# shield.net
KiCad netlist of a schematic drawn in EAGLE
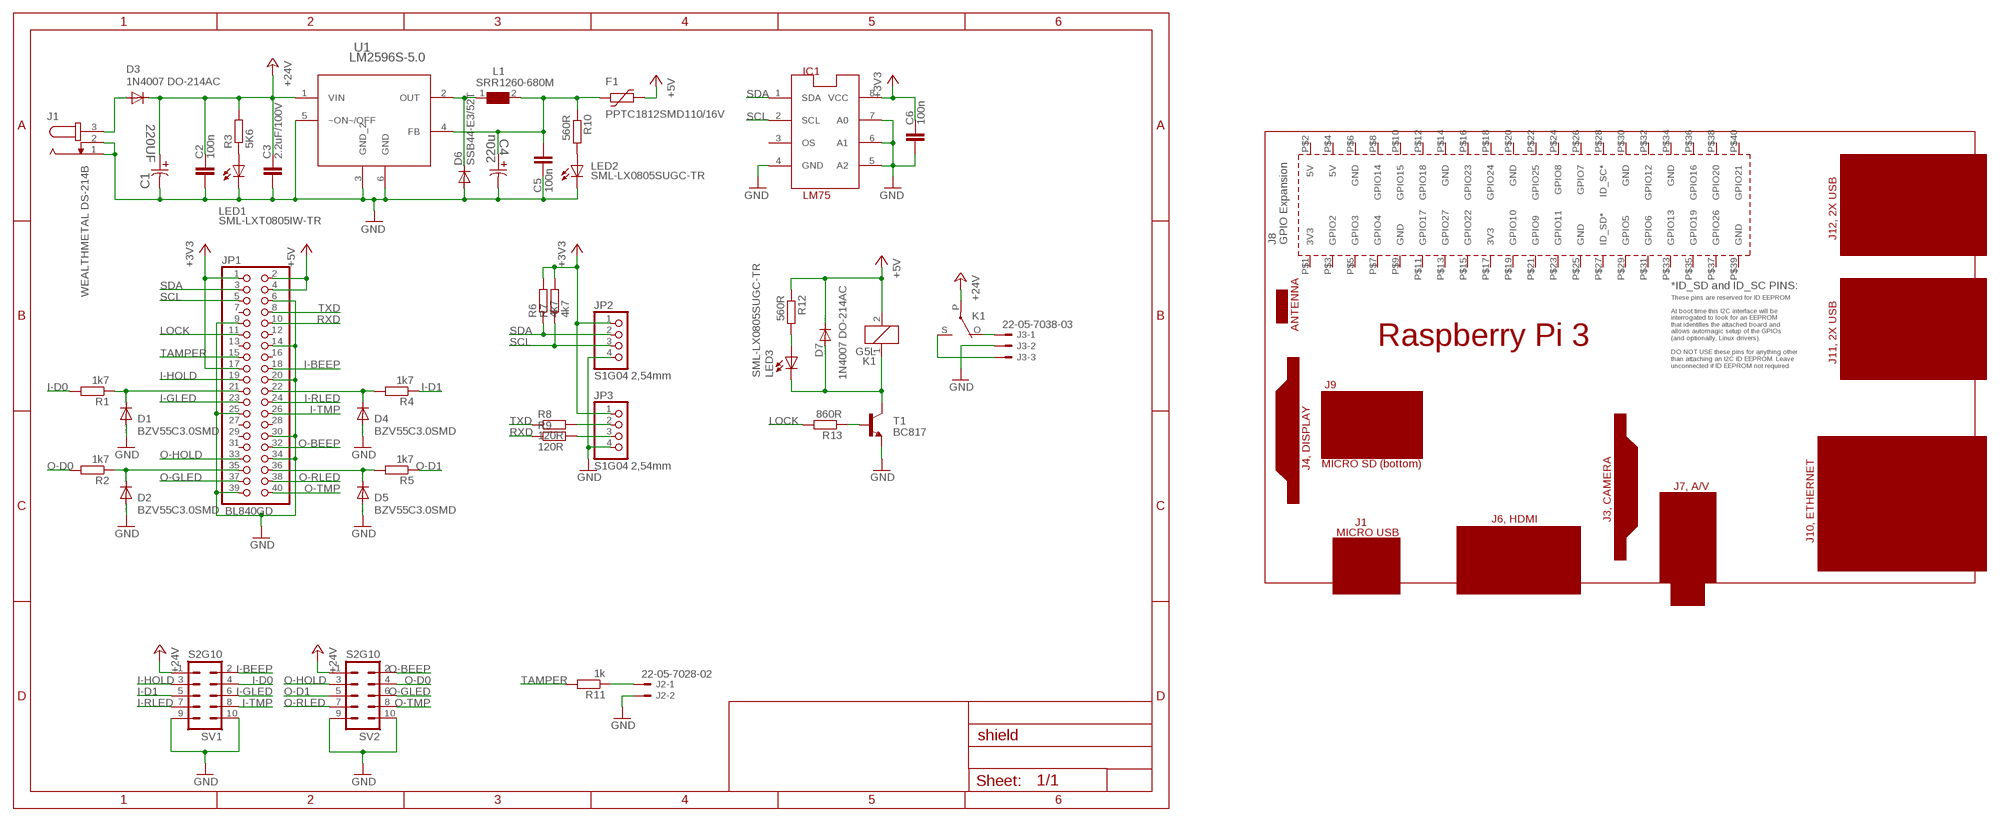
[diagram p0: schematic, sheet 1]

(export (version "E")
  (design (tool "Eeschema 10.0.6"))
  (components
    (comp (ref "C1")
      (value "220UF")
      (footprint "eagle-import:CAPAE830X1050N")
      (fields (field (name "MPN") "EEE-FP1V221AP") (field (name "TOLERANCE") "±20 %"))
      (libsource (lib "eagle-import") (part "EEE--CASE-FFP1V221AP"))
    )
    (comp (ref "C2")
      (value "100n")
      (footprint "eagle-import:C0805")
      (libsource (lib "eagle-import") (part "C-EUC0805"))
    )
    (comp (ref "C3")
      (value "2.2uF/100V")
      (footprint "eagle-import:C1206")
      (libsource (lib "eagle-import") (part "C-EUC1206"))
    )
    (comp (ref "C4")
      (value "220u")
      (footprint "eagle-import:CAPAE830X1050N")
      (fields (field (name "MPN") "EEE-FP1V221AP") (field (name "TOLERANCE") "±20 %"))
      (libsource (lib "eagle-import") (part "EEE--CASE-FFP1V221AP"))
    )
    (comp (ref "C5")
      (value "100n")
      (footprint "eagle-import:C0805")
      (libsource (lib "eagle-import") (part "C-EUC0805"))
    )
    (comp (ref "C6")
      (value "100n")
      (footprint "eagle-import:C0805")
      (libsource (lib "eagle-import") (part "C-EUC0805"))
    )
    (comp (ref "D1")
      (value "BZV55C3.0SMD")
      (footprint "eagle-import:MINIMELF")
      (libsource (lib "eagle-import") (part "DIODE-MINIMELF"))
    )
    (comp (ref "D2")
      (value "BZV55C3.0SMD")
      (footprint "eagle-import:MINIMELF")
      (libsource (lib "eagle-import") (part "DIODE-MINIMELF"))
    )
    (comp (ref "D3")
      (value "1N4007 DO-214AC")
      (footprint "eagle-import:DO-214AC")
      (libsource (lib "eagle-import") (part "DIODE-DO-214AC"))
    )
    (comp (ref "D4")
      (value "BZV55C3.0SMD")
      (footprint "eagle-import:MINIMELF")
      (libsource (lib "eagle-import") (part "DIODE-MINIMELF"))
    )
    (comp (ref "D5")
      (value "BZV55C3.0SMD")
      (footprint "eagle-import:MINIMELF")
      (libsource (lib "eagle-import") (part "DIODE-MINIMELF"))
    )
    (comp (ref "D6")
      (value "SSB44-E3/52T")
      (footprint "eagle-import:DO214AA")
      (libsource (lib "eagle-import") (part "DIODE-DO214AA"))
    )
    (comp (ref "D7")
      (value "1N4007 DO-214AC")
      (footprint "eagle-import:DO-214AC")
      (libsource (lib "eagle-import") (part "DIODE-DO-214AC"))
    )
    (comp (ref "F1")
      (value "PPTC1812SMD110/16V")
      (footprint "eagle-import:1812L")
      (libsource (lib "eagle-import") (part "1812L"))
    )
    (comp (ref "IC1")
      (value "LM75")
      (footprint "eagle-import:SO8_LM75")
      (libsource (lib "eagle-import") (part "LM75_ICN"))
    )
    (comp (ref "J1")
      (value "WEALTHMETAL DS-214B")
      (footprint "eagle-import:SPC4077")
      (libsource (lib "eagle-import") (part "JACK-PLUG0"))
    )
    (comp (ref "J2")
      (value "22-05-7028-02")
      (footprint "eagle-import:7395-02")
      (libsource (lib "eagle-import") (part "22-?-0205-7028"))
    )
    (comp (ref "J3")
      (value "22-05-7038-03")
      (footprint "eagle-import:7395-03")
      (libsource (lib "eagle-import") (part "22-?-0305-7038"))
    )
    (comp (ref "JP1")
      (value "BL840GD")
      (footprint "eagle-import:2X20")
      (libsource (lib "eagle-import") (part "PINHD-2X20"))
    )
    (comp (ref "JP2")
      (value "S1G04 2,54mm")
      (footprint "eagle-import:1X04")
      (libsource (lib "eagle-import") (part "PINHD-1X4"))
    )
    (comp (ref "JP3")
      (value "S1G04 2,54mm")
      (footprint "eagle-import:1X04")
      (libsource (lib "eagle-import") (part "PINHD-1X4"))
    )
    (comp (ref "K1")
      (value "G5L")
      (footprint "eagle-import:G5LE")
      (libsource (lib "eagle-import") (part "G5L"))
    )
    (comp (ref "L1")
      (value "SRR1260-680M")
      (footprint "eagle-import:WE-PD_1260_1245_1280_1210")
      (fields (field (name "MPN") "7447709680"))
      (libsource (lib "eagle-import") (part "WE-PD_1260/1245/1280/1210-7447709680"))
    )
    (comp (ref "LED1")
      (value "SML-LXT0805IW-TR")
      (footprint "eagle-import:CHIPLED_0805")
      (libsource (lib "eagle-import") (part "LEDCHIPLED_0805"))
    )
    (comp (ref "LED2")
      (value "SML-LX0805SUGC-TR")
      (footprint "eagle-import:CHIPLED_0805")
      (libsource (lib "eagle-import") (part "LEDCHIPLED_0805"))
    )
    (comp (ref "LED3")
      (value "SML-LX0805SUGC-TR")
      (footprint "eagle-import:CHIPLED_0805")
      (libsource (lib "eagle-import") (part "LEDCHIPLED_0805"))
    )
    (comp (ref "PCB1")
      (value "RPI3")
      (footprint "eagle-import:RPI3")
      (libsource (lib "eagle-import") (part "RPI3"))
    )
    (comp (ref "R1")
      (value "1k7")
      (footprint "eagle-import:R0805")
      (libsource (lib "eagle-import") (part "R-EU_R0805"))
    )
    (comp (ref "R2")
      (value "1k7")
      (footprint "eagle-import:R0805")
      (libsource (lib "eagle-import") (part "R-EU_R0805"))
    )
    (comp (ref "R3")
      (value "5K6")
      (footprint "eagle-import:R0805")
      (libsource (lib "eagle-import") (part "R-EU_R0805"))
    )
    (comp (ref "R4")
      (value "1k7")
      (footprint "eagle-import:R0805")
      (libsource (lib "eagle-import") (part "R-EU_R0805"))
    )
    (comp (ref "R5")
      (value "1k7")
      (footprint "eagle-import:R0805")
      (libsource (lib "eagle-import") (part "R-EU_R0805"))
    )
    (comp (ref "R6")
      (value "4k7")
      (footprint "eagle-import:R0805")
      (libsource (lib "eagle-import") (part "R-EU_R0805"))
    )
    (comp (ref "R7")
      (value "4k7")
      (footprint "eagle-import:R0805")
      (libsource (lib "eagle-import") (part "R-EU_R0805"))
    )
    (comp (ref "R8")
      (value "120R")
      (footprint "eagle-import:R0805")
      (libsource (lib "eagle-import") (part "R-EU_R0805"))
    )
    (comp (ref "R9")
      (value "120R")
      (footprint "eagle-import:R0805")
      (libsource (lib "eagle-import") (part "R-EU_R0805"))
    )
    (comp (ref "R10")
      (value "560R")
      (footprint "eagle-import:R0805")
      (libsource (lib "eagle-import") (part "R-EU_R0805"))
    )
    (comp (ref "R11")
      (value "1k")
      (footprint "eagle-import:R0805")
      (libsource (lib "eagle-import") (part "R-EU_R0805"))
    )
    (comp (ref "R12")
      (value "560R")
      (footprint "eagle-import:R0805")
      (libsource (lib "eagle-import") (part "R-EU_R0805"))
    )
    (comp (ref "R13")
      (value "860R")
      (footprint "eagle-import:R0805")
      (libsource (lib "eagle-import") (part "R-EU_R0805"))
    )
    (comp (ref "SV1")
      (value "S2G10")
      (footprint "eagle-import:MA05-2")
      (libsource (lib "eagle-import") (part "MA05-2"))
    )
    (comp (ref "SV2")
      (value "S2G10")
      (footprint "eagle-import:MA05-2")
      (libsource (lib "eagle-import") (part "MA05-2"))
    )
    (comp (ref "T1")
      (value "BC817")
      (footprint "eagle-import:SOT23-BEC")
      (libsource (lib "eagle-import") (part "-NPN-SOT23-BECBC817-16"))
    )
    (comp (ref "U1")
      (value "LM2596S-5.0")
      (footprint "eagle-import:TO170P1435X465-6N")
      (fields (field (name "MPN") "LM2596S-50"))
      (libsource (lib "eagle-import") (part "LM2596S-5.0"))
    )
  )
  (nets
    (net (code "1") (name "+3V3") (class "Default")
      (node (ref "C6") (pin "2") (pinfunction "2_2") (pintype "passive"))
      (node (ref "IC1") (pin "8") (pinfunction "VCC_8") (pintype "power_in"))
      (node (ref "JP1") (pin "1") (pinfunction "1_1") (pintype "passive"))
      (node (ref "JP1") (pin "17") (pinfunction "17_17") (pintype "passive"))
      (node (ref "JP2") (pin "1") (pinfunction "1_1") (pintype "passive"))
      (node (ref "JP3") (pin "1") (pinfunction "1_1") (pintype "passive"))
      (node (ref "R6") (pin "2") (pinfunction "2_2") (pintype "passive"))
      (node (ref "R7") (pin "2") (pinfunction "2_2") (pintype "passive"))
    )
    (net (code "2") (name "+5V") (class "Default")
      (node (ref "D7") (pin "C") (pinfunction "C_C") (pintype "passive"))
      (node (ref "F1") (pin "P$2") (pinfunction "2_P$2") (pintype "passive"))
      (node (ref "JP1") (pin "2") (pinfunction "2_2") (pintype "passive"))
      (node (ref "JP1") (pin "4") (pinfunction "4_4") (pintype "passive"))
      (node (ref "K1") (pin "2") (pinfunction "2_2") (pintype "passive"))
      (node (ref "R12") (pin "1") (pinfunction "1_1") (pintype "passive"))
    )
    (net (code "3") (name "+24V") (class "Default")
      (node (ref "C1") (pin "1") (pinfunction "1_1") (pintype "passive"))
      (node (ref "C2") (pin "2") (pinfunction "2_2") (pintype "passive"))
      (node (ref "C3") (pin "1") (pinfunction "1_1") (pintype "passive"))
      (node (ref "D3") (pin "C") (pinfunction "C_C") (pintype "passive"))
      (node (ref "K1") (pin "P") (pinfunction "P_P") (pintype "passive"))
      (node (ref "R3") (pin "2") (pinfunction "2_2") (pintype "passive"))
      (node (ref "SV1") (pin "1") (pinfunction "1_1") (pintype "passive"))
      (node (ref "SV2") (pin "1") (pinfunction "1_1") (pintype "passive"))
      (node (ref "U1") (pin "1") (pinfunction "VIN_1") (pintype "power_in"))
    )
    (net (code "4") (name "/I-BEEP") (class "Default")
      (node (ref "JP1") (pin "18") (pinfunction "18_18") (pintype "passive"))
      (node (ref "SV1") (pin "2") (pinfunction "2_2") (pintype "passive"))
    )
    (net (code "5") (name "/I-D0") (class "Default")
      (node (ref "R1") (pin "2") (pinfunction "2_2") (pintype "passive"))
      (node (ref "SV1") (pin "4") (pinfunction "4_4") (pintype "passive"))
    )
    (net (code "6") (name "/I-D1") (class "Default")
      (node (ref "R4") (pin "1") (pinfunction "1_1") (pintype "passive"))
      (node (ref "SV1") (pin "5") (pinfunction "5_5") (pintype "passive"))
    )
    (net (code "7") (name "/I-GLED") (class "Default")
      (node (ref "JP1") (pin "23") (pinfunction "23_23") (pintype "passive"))
      (node (ref "SV1") (pin "6") (pinfunction "6_6") (pintype "passive"))
    )
    (net (code "8") (name "/I-HOLD") (class "Default")
      (node (ref "JP1") (pin "19") (pinfunction "19_19") (pintype "passive"))
      (node (ref "SV1") (pin "3") (pinfunction "3_3") (pintype "passive"))
    )
    (net (code "9") (name "/I-RLED") (class "Default")
      (node (ref "JP1") (pin "24") (pinfunction "24_24") (pintype "passive"))
      (node (ref "SV1") (pin "7") (pinfunction "7_7") (pintype "passive"))
    )
    (net (code "10") (name "/I-TMP") (class "Default")
      (node (ref "JP1") (pin "26") (pinfunction "26_26") (pintype "passive"))
      (node (ref "SV1") (pin "8") (pinfunction "8_8") (pintype "passive"))
    )
    (net (code "11") (name "/LOCK") (class "Default")
      (node (ref "JP1") (pin "11") (pinfunction "11_11") (pintype "passive"))
      (node (ref "R13") (pin "2") (pinfunction "2_2") (pintype "passive"))
    )
    (net (code "12") (name "/O-BEEP") (class "Default")
      (node (ref "JP1") (pin "32") (pinfunction "32_32") (pintype "passive"))
      (node (ref "SV2") (pin "2") (pinfunction "2_2") (pintype "passive"))
    )
    (net (code "13") (name "/O-D0") (class "Default")
      (node (ref "R2") (pin "2") (pinfunction "2_2") (pintype "passive"))
      (node (ref "SV2") (pin "4") (pinfunction "4_4") (pintype "passive"))
    )
    (net (code "14") (name "/O-D1") (class "Default")
      (node (ref "R5") (pin "1") (pinfunction "1_1") (pintype "passive"))
      (node (ref "SV2") (pin "5") (pinfunction "5_5") (pintype "passive"))
    )
    (net (code "15") (name "/O-GLED") (class "Default")
      (node (ref "JP1") (pin "37") (pinfunction "37_37") (pintype "passive"))
      (node (ref "SV2") (pin "6") (pinfunction "6_6") (pintype "passive"))
    )
    (net (code "16") (name "/O-HOLD") (class "Default")
      (node (ref "JP1") (pin "33") (pinfunction "33_33") (pintype "passive"))
      (node (ref "SV2") (pin "3") (pinfunction "3_3") (pintype "passive"))
    )
    (net (code "17") (name "/O-RLED") (class "Default")
      (node (ref "JP1") (pin "38") (pinfunction "38_38") (pintype "passive"))
      (node (ref "SV2") (pin "7") (pinfunction "7_7") (pintype "passive"))
    )
    (net (code "18") (name "/O-TMP") (class "Default")
      (node (ref "JP1") (pin "40") (pinfunction "40_40") (pintype "passive"))
      (node (ref "SV2") (pin "8") (pinfunction "8_8") (pintype "passive"))
    )
    (net (code "19") (name "/RXD") (class "Default")
      (node (ref "JP1") (pin "10") (pinfunction "10_10") (pintype "passive"))
      (node (ref "R9") (pin "1") (pinfunction "1_1") (pintype "passive"))
    )
    (net (code "20") (name "/SCL") (class "Default")
      (node (ref "IC1") (pin "2") (pinfunction "SCL_2") (pintype "bidirectional"))
      (node (ref "JP1") (pin "5") (pinfunction "5_5") (pintype "passive"))
      (node (ref "JP2") (pin "3") (pinfunction "3_3") (pintype "passive"))
      (node (ref "R7") (pin "1") (pinfunction "1_1") (pintype "passive"))
    )
    (net (code "21") (name "/SDA") (class "Default")
      (node (ref "IC1") (pin "1") (pinfunction "SDA_1") (pintype "bidirectional"))
      (node (ref "JP1") (pin "3") (pinfunction "3_3") (pintype "passive"))
      (node (ref "JP2") (pin "2") (pinfunction "2_2") (pintype "passive"))
      (node (ref "R6") (pin "1") (pinfunction "1_1") (pintype "passive"))
    )
    (net (code "22") (name "/TAMPER") (class "Default")
      (node (ref "JP1") (pin "15") (pinfunction "15_15") (pintype "passive"))
      (node (ref "R11") (pin "2") (pinfunction "2_2") (pintype "passive"))
    )
    (net (code "23") (name "/TXD") (class "Default")
      (node (ref "JP1") (pin "8") (pinfunction "8_8") (pintype "passive"))
      (node (ref "R8") (pin "1") (pinfunction "1_1") (pintype "passive"))
    )
    (net (code "24") (name "GND") (class "Default")
      (node (ref "C1") (pin "2") (pinfunction "2_2") (pintype "passive"))
      (node (ref "C2") (pin "1") (pinfunction "1_1") (pintype "passive"))
      (node (ref "C3") (pin "2") (pinfunction "2_2") (pintype "passive"))
      (node (ref "C4") (pin "2") (pinfunction "2_2") (pintype "passive"))
      (node (ref "C5") (pin "1") (pinfunction "1_1") (pintype "passive"))
      (node (ref "C6") (pin "1") (pinfunction "1_1") (pintype "passive"))
      (node (ref "D1") (pin "A") (pinfunction "A_A") (pintype "passive"))
      (node (ref "D2") (pin "A") (pinfunction "A_A") (pintype "passive"))
      (node (ref "D4") (pin "A") (pinfunction "A_A") (pintype "passive"))
      (node (ref "D5") (pin "A") (pinfunction "A_A") (pintype "passive"))
      (node (ref "D6") (pin "A") (pinfunction "A_A") (pintype "passive"))
      (node (ref "IC1") (pin "4") (pinfunction "GND_4") (pintype "power_in"))
      (node (ref "IC1") (pin "5") (pinfunction "A2_5") (pintype "input"))
      (node (ref "IC1") (pin "6") (pinfunction "A1_6") (pintype "input"))
      (node (ref "IC1") (pin "7") (pinfunction "A0_7") (pintype "input"))
      (node (ref "J1") (pin "1") (pinfunction "1_1") (pintype "passive"))
      (node (ref "J1") (pin "2") (pinfunction "2_2") (pintype "passive"))
      (node (ref "J2") (pin "2") (pinfunction "S_2") (pintype "passive"))
      (node (ref "J3") (pin "2") (pinfunction "S_2") (pintype "passive"))
      (node (ref "JP1") (pin "14") (pinfunction "14_14") (pintype "passive"))
      (node (ref "JP1") (pin "20") (pinfunction "20_20") (pintype "passive"))
      (node (ref "JP1") (pin "25") (pinfunction "25_25") (pintype "passive"))
      (node (ref "JP1") (pin "30") (pinfunction "30_30") (pintype "passive"))
      (node (ref "JP1") (pin "34") (pinfunction "34_34") (pintype "passive"))
      (node (ref "JP1") (pin "39") (pinfunction "39_39") (pintype "passive"))
      (node (ref "JP1") (pin "6") (pinfunction "6_6") (pintype "passive"))
      (node (ref "JP1") (pin "9") (pinfunction "9_9") (pintype "passive"))
      (node (ref "JP2") (pin "4") (pinfunction "4_4") (pintype "passive"))
      (node (ref "JP3") (pin "4") (pinfunction "4_4") (pintype "passive"))
      (node (ref "LED1") (pin "C") (pinfunction "C_C") (pintype "passive"))
      (node (ref "LED2") (pin "C") (pinfunction "C_C") (pintype "passive"))
      (node (ref "SV1") (pin "10") (pinfunction "10_10") (pintype "passive"))
      (node (ref "SV1") (pin "9") (pinfunction "9_9") (pintype "passive"))
      (node (ref "SV2") (pin "10") (pinfunction "10_10") (pintype "passive"))
      (node (ref "SV2") (pin "9") (pinfunction "9_9") (pintype "passive"))
      (node (ref "T1") (pin "E") (pinfunction "E_E") (pintype "passive"))
      (node (ref "U1") (pin "3") (pinfunction "GND_2_3") (pintype "passive"))
      (node (ref "U1") (pin "5") (pinfunction "~{ON}/OFF_5") (pintype "input"))
      (node (ref "U1") (pin "6") (pinfunction "GND_6") (pintype "passive"))
    )
    (net (code "25") (name "Net-(D1-PadC)") (class "Default")
      (node (ref "D1") (pin "C") (pinfunction "C_C") (pintype "passive"))
      (node (ref "JP1") (pin "21") (pinfunction "21_21") (pintype "passive"))
      (node (ref "R1") (pin "1") (pinfunction "1_1") (pintype "passive"))
    )
    (net (code "26") (name "Net-(D2-PadC)") (class "Default")
      (node (ref "D2") (pin "C") (pinfunction "C_C") (pintype "passive"))
      (node (ref "JP1") (pin "35") (pinfunction "35_35") (pintype "passive"))
      (node (ref "R2") (pin "1") (pinfunction "1_1") (pintype "passive"))
    )
    (net (code "27") (name "Net-(D3-PadA)") (class "Default")
      (node (ref "D3") (pin "A") (pinfunction "A_A") (pintype "passive"))
      (node (ref "J1") (pin "3") (pinfunction "3_3") (pintype "passive"))
    )
    (net (code "28") (name "Net-(D4-PadC)") (class "Default")
      (node (ref "D4") (pin "C") (pinfunction "C_C") (pintype "passive"))
      (node (ref "JP1") (pin "22") (pinfunction "22_22") (pintype "passive"))
      (node (ref "R4") (pin "2") (pinfunction "2_2") (pintype "passive"))
    )
    (net (code "29") (name "Net-(D5-PadC)") (class "Default")
      (node (ref "D5") (pin "C") (pinfunction "C_C") (pintype "passive"))
      (node (ref "JP1") (pin "36") (pinfunction "36_36") (pintype "passive"))
      (node (ref "R5") (pin "2") (pinfunction "2_2") (pintype "passive"))
    )
    (net (code "30") (name "Net-(D7-PadA)") (class "Default")
      (node (ref "D7") (pin "A") (pinfunction "A_A") (pintype "passive"))
      (node (ref "K1") (pin "1") (pinfunction "1_1") (pintype "passive"))
      (node (ref "LED3") (pin "C") (pinfunction "C_C") (pintype "passive"))
      (node (ref "T1") (pin "C") (pinfunction "C_C") (pintype "passive"))
    )
    (net (code "31") (name "Net-(F1-1)") (class "Default")
      (node (ref "C4") (pin "1") (pinfunction "1_1") (pintype "passive"))
      (node (ref "C5") (pin "2") (pinfunction "2_2") (pintype "passive"))
      (node (ref "F1") (pin "P$1") (pinfunction "1_P$1") (pintype "passive"))
      (node (ref "L1") (pin "2") (pinfunction "2_2") (pintype "passive"))
      (node (ref "R10") (pin "1") (pinfunction "1_1") (pintype "passive"))
      (node (ref "U1") (pin "4") (pinfunction "FB_4") (pintype "input"))
    )
    (net (code "32") (name "Net-(J2A-S)") (class "Default")
      (node (ref "J2") (pin "1") (pinfunction "S_1") (pintype "passive"))
      (node (ref "R11") (pin "1") (pinfunction "1_1") (pintype "passive"))
    )
    (net (code "33") (name "Net-(J3A-S)") (class "Default")
      (node (ref "J3") (pin "1") (pinfunction "S_1") (pintype "passive"))
      (node (ref "K1") (pin "O") (pinfunction "O_O") (pintype "passive"))
    )
    (net (code "34") (name "Net-(J3C-S)") (class "Default")
      (node (ref "J3") (pin "3") (pinfunction "S_3") (pintype "passive"))
      (node (ref "K1") (pin "S") (pinfunction "S_S") (pintype "passive"))
    )
    (net (code "35") (name "Net-(JP3-Pad2)") (class "Default")
      (node (ref "JP3") (pin "2") (pinfunction "2_2") (pintype "passive"))
      (node (ref "R8") (pin "2") (pinfunction "2_2") (pintype "passive"))
    )
    (net (code "36") (name "Net-(JP3-Pad3)") (class "Default")
      (node (ref "JP3") (pin "3") (pinfunction "3_3") (pintype "passive"))
      (node (ref "R9") (pin "2") (pinfunction "2_2") (pintype "passive"))
    )
    (net (code "37") (name "Net-(LED1-PadA)") (class "Default")
      (node (ref "LED1") (pin "A") (pinfunction "A_A") (pintype "passive"))
      (node (ref "R3") (pin "1") (pinfunction "1_1") (pintype "passive"))
    )
    (net (code "38") (name "Net-(LED2-PadA)") (class "Default")
      (node (ref "LED2") (pin "A") (pinfunction "A_A") (pintype "passive"))
      (node (ref "R10") (pin "2") (pinfunction "2_2") (pintype "passive"))
    )
    (net (code "39") (name "Net-(LED3-PadA)") (class "Default")
      (node (ref "LED3") (pin "A") (pinfunction "A_A") (pintype "passive"))
      (node (ref "R12") (pin "2") (pinfunction "2_2") (pintype "passive"))
    )
    (net (code "40") (name "Net-(R13-Pad1)") (class "Default")
      (node (ref "R13") (pin "1") (pinfunction "1_1") (pintype "passive"))
      (node (ref "T1") (pin "B") (pinfunction "B_B") (pintype "passive"))
    )
    (net (code "41") (name "Net-(U1-OUT)") (class "Default")
      (node (ref "D6") (pin "C") (pinfunction "C_C") (pintype "passive"))
      (node (ref "L1") (pin "1") (pinfunction "1_1") (pintype "passive"))
      (node (ref "U1") (pin "2") (pinfunction "OUT_2") (pintype "output"))
    )
    (net (code "42") (name "unconnected-(IC1-OS-Pad3)") (class "Default")
      (node (ref "IC1") (pin "3") (pinfunction "OS_3") (pintype "output"))
    )
    (net (code "43") (name "unconnected-(JP1-Pad7)") (class "Default")
      (node (ref "JP1") (pin "7") (pinfunction "7_7") (pintype "passive"))
    )
    (net (code "44") (name "unconnected-(JP1-Pad12)") (class "Default")
      (node (ref "JP1") (pin "12") (pinfunction "12_12") (pintype "passive"))
    )
    (net (code "45") (name "unconnected-(JP1-Pad13)") (class "Default")
      (node (ref "JP1") (pin "13") (pinfunction "13_13") (pintype "passive"))
    )
    (net (code "46") (name "unconnected-(JP1-Pad16)") (class "Default")
      (node (ref "JP1") (pin "16") (pinfunction "16_16") (pintype "passive"))
    )
    (net (code "47") (name "unconnected-(JP1-Pad27)") (class "Default")
      (node (ref "JP1") (pin "27") (pinfunction "27_27") (pintype "passive"))
    )
    (net (code "48") (name "unconnected-(JP1-Pad28)") (class "Default")
      (node (ref "JP1") (pin "28") (pinfunction "28_28") (pintype "passive"))
    )
    (net (code "49") (name "unconnected-(JP1-Pad29)") (class "Default")
      (node (ref "JP1") (pin "29") (pinfunction "29_29") (pintype "passive"))
    )
    (net (code "50") (name "unconnected-(JP1-Pad31)") (class "Default")
      (node (ref "JP1") (pin "31") (pinfunction "31_31") (pintype "passive"))
    )
    (net (code "51") (name "unconnected-(PCB1-3V3-PadP$1)") (class "Default")
      (node (ref "PCB1") (pin "P$1") (pinfunction "3V3_P$1") (pintype "bidirectional"))
    )
    (net (code "52") (name "unconnected-(PCB1-3V3-PadP$17)") (class "Default")
      (node (ref "PCB1") (pin "P$17") (pinfunction "3V3_P$17") (pintype "bidirectional"))
    )
    (net (code "53") (name "unconnected-(PCB1-5V-PadP$2)") (class "Default")
      (node (ref "PCB1") (pin "P$2") (pinfunction "5V_P$2") (pintype "bidirectional"))
    )
    (net (code "54") (name "unconnected-(PCB1-5V-PadP$4)") (class "Default")
      (node (ref "PCB1") (pin "P$4") (pinfunction "5V_P$4") (pintype "bidirectional"))
    )
    (net (code "55") (name "unconnected-(PCB1-GND-PadP$6)") (class "Default")
      (node (ref "PCB1") (pin "P$6") (pinfunction "GND_P$6") (pintype "bidirectional"))
    )
    (net (code "56") (name "unconnected-(PCB1-GND-PadP$9)") (class "Default")
      (node (ref "PCB1") (pin "P$9") (pinfunction "GND_P$9") (pintype "bidirectional"))
    )
    (net (code "57") (name "unconnected-(PCB1-GND-PadP$14)") (class "Default")
      (node (ref "PCB1") (pin "P$14") (pinfunction "GND_P$14") (pintype "bidirectional"))
    )
    (net (code "58") (name "unconnected-(PCB1-GND-PadP$20)") (class "Default")
      (node (ref "PCB1") (pin "P$20") (pinfunction "GND_P$20") (pintype "bidirectional"))
    )
    (net (code "59") (name "unconnected-(PCB1-GND-PadP$25)") (class "Default")
      (node (ref "PCB1") (pin "P$25") (pinfunction "GND_P$25") (pintype "bidirectional"))
    )
    (net (code "60") (name "unconnected-(PCB1-GND-PadP$30)") (class "Default")
      (node (ref "PCB1") (pin "P$30") (pinfunction "GND_P$30") (pintype "bidirectional"))
    )
    (net (code "61") (name "unconnected-(PCB1-GND-PadP$34)") (class "Default")
      (node (ref "PCB1") (pin "P$34") (pinfunction "GND_P$34") (pintype "bidirectional"))
    )
    (net (code "62") (name "unconnected-(PCB1-GND-PadP$39)") (class "Default")
      (node (ref "PCB1") (pin "P$39") (pinfunction "GND_P$39") (pintype "bidirectional"))
    )
    (net (code "63") (name "unconnected-(PCB1-GPIO2-PadP$3)") (class "Default")
      (node (ref "PCB1") (pin "P$3") (pinfunction "GPIO2_P$3") (pintype "bidirectional"))
    )
    (net (code "64") (name "unconnected-(PCB1-GPIO3-PadP$5)") (class "Default")
      (node (ref "PCB1") (pin "P$5") (pinfunction "GPIO3_P$5") (pintype "bidirectional"))
    )
    (net (code "65") (name "unconnected-(PCB1-GPIO4-PadP$7)") (class "Default")
      (node (ref "PCB1") (pin "P$7") (pinfunction "GPIO4_P$7") (pintype "bidirectional"))
    )
    (net (code "66") (name "unconnected-(PCB1-GPIO5-PadP$29)") (class "Default")
      (node (ref "PCB1") (pin "P$29") (pinfunction "GPIO5_P$29") (pintype "bidirectional"))
    )
    (net (code "67") (name "unconnected-(PCB1-GPIO6-PadP$31)") (class "Default")
      (node (ref "PCB1") (pin "P$31") (pinfunction "GPIO6_P$31") (pintype "bidirectional"))
    )
    (net (code "68") (name "unconnected-(PCB1-GPIO7-PadP$26)") (class "Default")
      (node (ref "PCB1") (pin "P$26") (pinfunction "GPIO7_P$26") (pintype "bidirectional"))
    )
    (net (code "69") (name "unconnected-(PCB1-GPIO8-PadP$24)") (class "Default")
      (node (ref "PCB1") (pin "P$24") (pinfunction "GPIO8_P$24") (pintype "bidirectional"))
    )
    (net (code "70") (name "unconnected-(PCB1-GPIO9-PadP$21)") (class "Default")
      (node (ref "PCB1") (pin "P$21") (pinfunction "GPIO9_P$21") (pintype "bidirectional"))
    )
    (net (code "71") (name "unconnected-(PCB1-GPIO10-PadP$19)") (class "Default")
      (node (ref "PCB1") (pin "P$19") (pinfunction "GPIO10_P$19") (pintype "bidirectional"))
    )
    (net (code "72") (name "unconnected-(PCB1-GPIO11-PadP$23)") (class "Default")
      (node (ref "PCB1") (pin "P$23") (pinfunction "GPIO11_P$23") (pintype "bidirectional"))
    )
    (net (code "73") (name "unconnected-(PCB1-GPIO12-PadP$32)") (class "Default")
      (node (ref "PCB1") (pin "P$32") (pinfunction "GPIO12_P$32") (pintype "bidirectional"))
    )
    (net (code "74") (name "unconnected-(PCB1-GPIO13-PadP$33)") (class "Default")
      (node (ref "PCB1") (pin "P$33") (pinfunction "GPIO13_P$33") (pintype "bidirectional"))
    )
    (net (code "75") (name "unconnected-(PCB1-GPIO14-PadP$8)") (class "Default")
      (node (ref "PCB1") (pin "P$8") (pinfunction "GPIO14_P$8") (pintype "bidirectional"))
    )
    (net (code "76") (name "unconnected-(PCB1-GPIO15-PadP$10)") (class "Default")
      (node (ref "PCB1") (pin "P$10") (pinfunction "GPIO15_P$10") (pintype "bidirectional"))
    )
    (net (code "77") (name "unconnected-(PCB1-GPIO16-PadP$36)") (class "Default")
      (node (ref "PCB1") (pin "P$36") (pinfunction "GPIO16_P$36") (pintype "bidirectional"))
    )
    (net (code "78") (name "unconnected-(PCB1-GPIO17-PadP$11)") (class "Default")
      (node (ref "PCB1") (pin "P$11") (pinfunction "GPIO17_P$11") (pintype "bidirectional"))
    )
    (net (code "79") (name "unconnected-(PCB1-GPIO18-PadP$12)") (class "Default")
      (node (ref "PCB1") (pin "P$12") (pinfunction "GPIO18_P$12") (pintype "bidirectional"))
    )
    (net (code "80") (name "unconnected-(PCB1-GPIO19-PadP$35)") (class "Default")
      (node (ref "PCB1") (pin "P$35") (pinfunction "GPIO19_P$35") (pintype "bidirectional"))
    )
    (net (code "81") (name "unconnected-(PCB1-GPIO20-PadP$38)") (class "Default")
      (node (ref "PCB1") (pin "P$38") (pinfunction "GPIO20_P$38") (pintype "bidirectional"))
    )
    (net (code "82") (name "unconnected-(PCB1-GPIO21-PadP$40)") (class "Default")
      (node (ref "PCB1") (pin "P$40") (pinfunction "GPIO21_P$40") (pintype "bidirectional"))
    )
    (net (code "83") (name "unconnected-(PCB1-GPIO22-PadP$15)") (class "Default")
      (node (ref "PCB1") (pin "P$15") (pinfunction "GPIO22_P$15") (pintype "bidirectional"))
    )
    (net (code "84") (name "unconnected-(PCB1-GPIO23-PadP$16)") (class "Default")
      (node (ref "PCB1") (pin "P$16") (pinfunction "GPIO23_P$16") (pintype "bidirectional"))
    )
    (net (code "85") (name "unconnected-(PCB1-GPIO24-PadP$18)") (class "Default")
      (node (ref "PCB1") (pin "P$18") (pinfunction "GPIO24_P$18") (pintype "bidirectional"))
    )
    (net (code "86") (name "unconnected-(PCB1-GPIO25-PadP$22)") (class "Default")
      (node (ref "PCB1") (pin "P$22") (pinfunction "GPIO25_P$22") (pintype "bidirectional"))
    )
    (net (code "87") (name "unconnected-(PCB1-GPIO26-PadP$37)") (class "Default")
      (node (ref "PCB1") (pin "P$37") (pinfunction "GPIO26_P$37") (pintype "bidirectional"))
    )
    (net (code "88") (name "unconnected-(PCB1-GPIO27-PadP$13)") (class "Default")
      (node (ref "PCB1") (pin "P$13") (pinfunction "GPIO27_P$13") (pintype "bidirectional"))
    )
    (net (code "89") (name "unconnected-(PCB1-ID_SC*-PadP$28)") (class "Default")
      (node (ref "PCB1") (pin "P$28") (pinfunction "ID_SC*_P$28") (pintype "bidirectional"))
    )
    (net (code "90") (name "unconnected-(PCB1-ID_SD*-PadP$27)") (class "Default")
      (node (ref "PCB1") (pin "P$27") (pinfunction "ID_SD*_P$27") (pintype "bidirectional"))
    )
  )
)
